# Connectors.net
KiCad netlist of a schematic drawn in Altium Designer
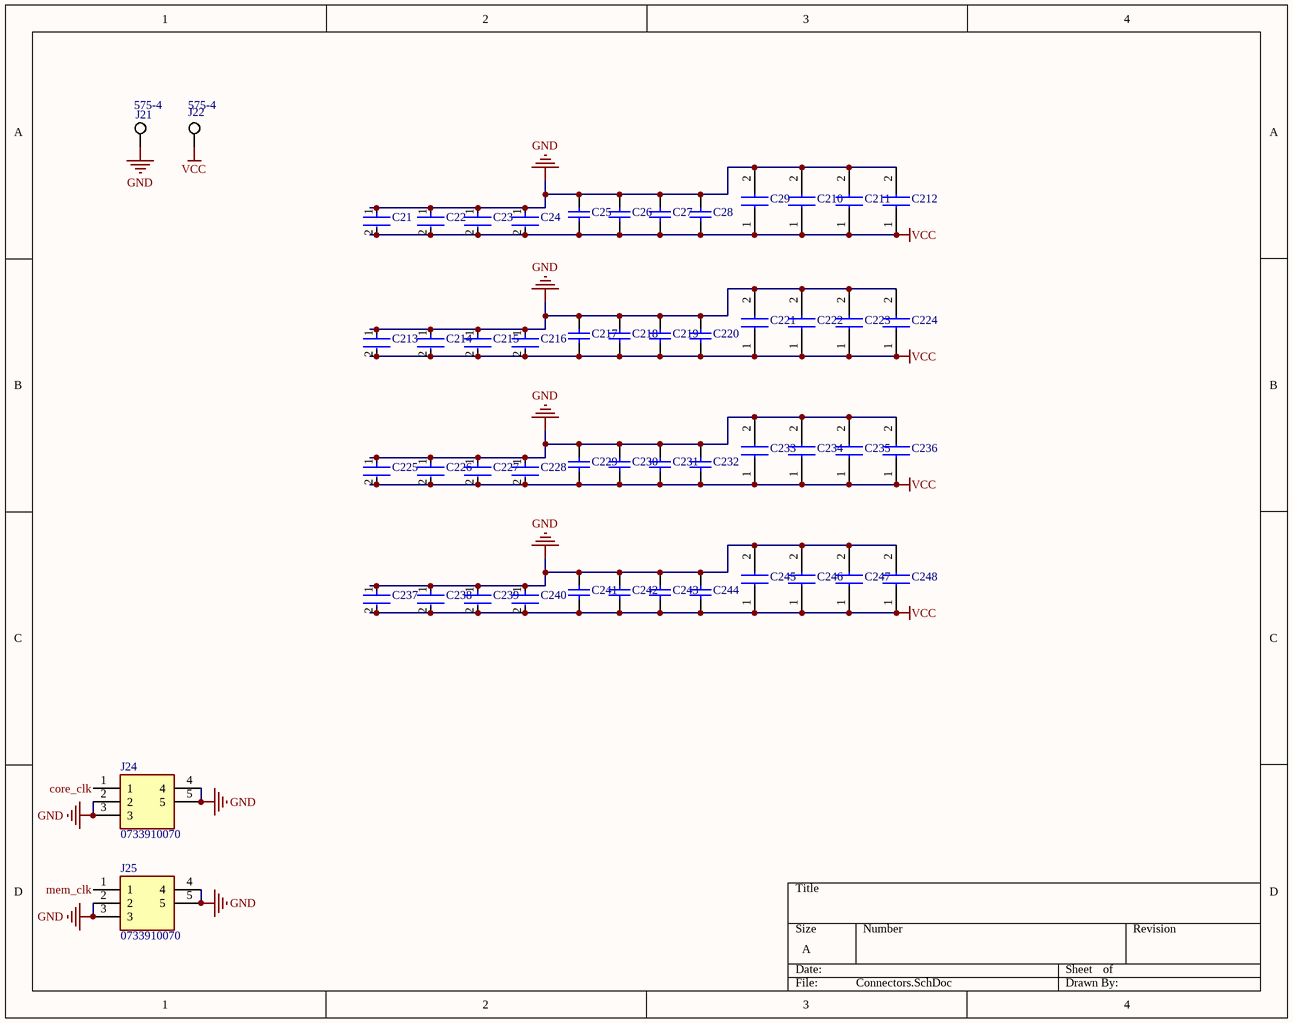
[diagram p0: Connectors.SchDoc]

(export (version "E")
  (design (tool "Eeschema 10.0.6"))
  (components
    (comp (ref "C21")
      (value "UMK105BJ104KV-F")
      (footprint "FP-0402-L_1_0_0_05-W_0_5-IPC_B")
      (description "None")
      (fields (field (name "TOLERANCE") "10%"))
      (libsource (lib "Altium Content Vault") (part "b4654b650e69147ec39a6b967a45e02"))
    )
    (comp (ref "C22")
      (value "UMK105BJ104KV-F")
      (footprint "FP-0402-L_1_0_0_05-W_0_5-IPC_B")
      (description "None")
      (fields (field (name "TOLERANCE") "10%"))
      (libsource (lib "Altium Content Vault") (part "b4654b650e69147ec39a6b967a45e02"))
    )
    (comp (ref "C23")
      (value "UMK105BJ104KV-F")
      (footprint "FP-0402-L_1_0_0_05-W_0_5-IPC_B")
      (description "None")
      (fields (field (name "TOLERANCE") "10%"))
      (libsource (lib "Altium Content Vault") (part "b4654b650e69147ec39a6b967a45e02"))
    )
    (comp (ref "C24")
      (value "UMK105BJ104KV-F")
      (footprint "FP-0402-L_1_0_0_05-W_0_5-IPC_B")
      (description "None")
      (fields (field (name "TOLERANCE") "10%"))
      (libsource (lib "Altium Content Vault") (part "b4654b650e69147ec39a6b967a45e02"))
    )
    (comp (ref "C25")
      (value "LMK107B7105KA-T")
      (footprint "CAPC1608X90X35NL10T25")
      (description "None")
      (fields (field (name "TOLERANCE") "10%"))
      (libsource (lib "Altium Content Vault") (part "CAP-NP-2"))
    )
    (comp (ref "C26")
      (value "LMK107B7105KA-T")
      (footprint "CAPC1608X90X35NL10T25")
      (description "None")
      (fields (field (name "TOLERANCE") "10%"))
      (libsource (lib "Altium Content Vault") (part "CAP-NP-2"))
    )
    (comp (ref "C27")
      (value "LMK107B7105KA-T")
      (footprint "CAPC1608X90X35NL10T25")
      (description "None")
      (fields (field (name "TOLERANCE") "10%"))
      (libsource (lib "Altium Content Vault") (part "CAP-NP-2"))
    )
    (comp (ref "C28")
      (value "LMK107B7105KA-T")
      (footprint "CAPC1608X90X35NL10T25")
      (description "None")
      (fields (field (name "TOLERANCE") "10%"))
      (libsource (lib "Altium Content Vault") (part "CAP-NP-2"))
    )
    (comp (ref "C29")
      (value "KGM15CR51A106MT")
      (footprint "SamacSys:CAPC1608X100N")
      (description "Capacitor")
      (libsource (lib "*") (part "KGM15CR51A106MT"))
    )
    (comp (ref "C210")
      (value "KGM15CR51A106MT")
      (footprint "SamacSys:CAPC1608X100N")
      (description "Capacitor")
      (libsource (lib "*") (part "KGM15CR51A106MT"))
    )
    (comp (ref "C211")
      (value "KGM15CR51A106MT")
      (footprint "SamacSys:CAPC1608X100N")
      (description "Capacitor")
      (libsource (lib "*") (part "KGM15CR51A106MT"))
    )
    (comp (ref "C212")
      (value "KGM15CR51A106MT")
      (footprint "SamacSys:CAPC1608X100N")
      (description "Capacitor")
      (libsource (lib "*") (part "KGM15CR51A106MT"))
    )
    (comp (ref "C213")
      (value "UMK105BJ104KV-F")
      (footprint "FP-0402-L_1_0_0_05-W_0_5-IPC_B")
      (description "None")
      (fields (field (name "TOLERANCE") "10%"))
      (libsource (lib "Altium Content Vault") (part "b4654b650e69147ec39a6b967a45e02"))
    )
    (comp (ref "C214")
      (value "UMK105BJ104KV-F")
      (footprint "FP-0402-L_1_0_0_05-W_0_5-IPC_B")
      (description "None")
      (fields (field (name "TOLERANCE") "10%"))
      (libsource (lib "Altium Content Vault") (part "b4654b650e69147ec39a6b967a45e02"))
    )
    (comp (ref "C215")
      (value "UMK105BJ104KV-F")
      (footprint "FP-0402-L_1_0_0_05-W_0_5-IPC_B")
      (description "None")
      (fields (field (name "TOLERANCE") "10%"))
      (libsource (lib "Altium Content Vault") (part "b4654b650e69147ec39a6b967a45e02"))
    )
    (comp (ref "C216")
      (value "UMK105BJ104KV-F")
      (footprint "FP-0402-L_1_0_0_05-W_0_5-IPC_B")
      (description "None")
      (fields (field (name "TOLERANCE") "10%"))
      (libsource (lib "Altium Content Vault") (part "b4654b650e69147ec39a6b967a45e02"))
    )
    (comp (ref "C217")
      (value "LMK107B7105KA-T")
      (footprint "CAPC1608X90X35NL10T25")
      (description "None")
      (fields (field (name "TOLERANCE") "10%"))
      (libsource (lib "Altium Content Vault") (part "CAP-NP-2"))
    )
    (comp (ref "C218")
      (value "LMK107B7105KA-T")
      (footprint "CAPC1608X90X35NL10T25")
      (description "None")
      (fields (field (name "TOLERANCE") "10%"))
      (libsource (lib "Altium Content Vault") (part "CAP-NP-2"))
    )
    (comp (ref "C219")
      (value "LMK107B7105KA-T")
      (footprint "CAPC1608X90X35NL10T25")
      (description "None")
      (fields (field (name "TOLERANCE") "10%"))
      (libsource (lib "Altium Content Vault") (part "CAP-NP-2"))
    )
    (comp (ref "C220")
      (value "LMK107B7105KA-T")
      (footprint "CAPC1608X90X35NL10T25")
      (description "None")
      (fields (field (name "TOLERANCE") "10%"))
      (libsource (lib "Altium Content Vault") (part "CAP-NP-2"))
    )
    (comp (ref "C221")
      (value "KGM15CR51A106MT")
      (footprint "SamacSys:CAPC1608X100N")
      (description "Capacitor")
      (libsource (lib "*") (part "KGM15CR51A106MT"))
    )
    (comp (ref "C222")
      (value "KGM15CR51A106MT")
      (footprint "SamacSys:CAPC1608X100N")
      (description "Capacitor")
      (libsource (lib "*") (part "KGM15CR51A106MT"))
    )
    (comp (ref "C223")
      (value "KGM15CR51A106MT")
      (footprint "SamacSys:CAPC1608X100N")
      (description "Capacitor")
      (libsource (lib "*") (part "KGM15CR51A106MT"))
    )
    (comp (ref "C224")
      (value "KGM15CR51A106MT")
      (footprint "SamacSys:CAPC1608X100N")
      (description "Capacitor")
      (libsource (lib "*") (part "KGM15CR51A106MT"))
    )
    (comp (ref "C225")
      (value "UMK105BJ104KV-F")
      (footprint "FP-0402-L_1_0_0_05-W_0_5-IPC_B")
      (description "None")
      (fields (field (name "TOLERANCE") "10%"))
      (libsource (lib "Altium Content Vault") (part "b4654b650e69147ec39a6b967a45e02"))
    )
    (comp (ref "C226")
      (value "UMK105BJ104KV-F")
      (footprint "FP-0402-L_1_0_0_05-W_0_5-IPC_B")
      (description "None")
      (fields (field (name "TOLERANCE") "10%"))
      (libsource (lib "Altium Content Vault") (part "b4654b650e69147ec39a6b967a45e02"))
    )
    (comp (ref "C227")
      (value "UMK105BJ104KV-F")
      (footprint "FP-0402-L_1_0_0_05-W_0_5-IPC_B")
      (description "None")
      (fields (field (name "TOLERANCE") "10%"))
      (libsource (lib "Altium Content Vault") (part "b4654b650e69147ec39a6b967a45e02"))
    )
    (comp (ref "C228")
      (value "UMK105BJ104KV-F")
      (footprint "FP-0402-L_1_0_0_05-W_0_5-IPC_B")
      (description "None")
      (fields (field (name "TOLERANCE") "10%"))
      (libsource (lib "Altium Content Vault") (part "b4654b650e69147ec39a6b967a45e02"))
    )
    (comp (ref "C229")
      (value "LMK107B7105KA-T")
      (footprint "CAPC1608X90X35NL10T25")
      (description "None")
      (fields (field (name "TOLERANCE") "10%"))
      (libsource (lib "Altium Content Vault") (part "CAP-NP-2"))
    )
    (comp (ref "C230")
      (value "LMK107B7105KA-T")
      (footprint "CAPC1608X90X35NL10T25")
      (description "None")
      (fields (field (name "TOLERANCE") "10%"))
      (libsource (lib "Altium Content Vault") (part "CAP-NP-2"))
    )
    (comp (ref "C231")
      (value "LMK107B7105KA-T")
      (footprint "CAPC1608X90X35NL10T25")
      (description "None")
      (fields (field (name "TOLERANCE") "10%"))
      (libsource (lib "Altium Content Vault") (part "CAP-NP-2"))
    )
    (comp (ref "C232")
      (value "LMK107B7105KA-T")
      (footprint "CAPC1608X90X35NL10T25")
      (description "None")
      (fields (field (name "TOLERANCE") "10%"))
      (libsource (lib "Altium Content Vault") (part "CAP-NP-2"))
    )
    (comp (ref "C233")
      (value "KGM15CR51A106MT")
      (footprint "SamacSys:CAPC1608X100N")
      (description "Capacitor")
      (libsource (lib "*") (part "KGM15CR51A106MT"))
    )
    (comp (ref "C234")
      (value "KGM15CR51A106MT")
      (footprint "SamacSys:CAPC1608X100N")
      (description "Capacitor")
      (libsource (lib "*") (part "KGM15CR51A106MT"))
    )
    (comp (ref "C235")
      (value "KGM15CR51A106MT")
      (footprint "SamacSys:CAPC1608X100N")
      (description "Capacitor")
      (libsource (lib "*") (part "KGM15CR51A106MT"))
    )
    (comp (ref "C236")
      (value "KGM15CR51A106MT")
      (footprint "SamacSys:CAPC1608X100N")
      (description "Capacitor")
      (libsource (lib "*") (part "KGM15CR51A106MT"))
    )
    (comp (ref "C237")
      (value "UMK105BJ104KV-F")
      (footprint "FP-0402-L_1_0_0_05-W_0_5-IPC_B")
      (description "None")
      (fields (field (name "TOLERANCE") "10%"))
      (libsource (lib "Altium Content Vault") (part "b4654b650e69147ec39a6b967a45e02"))
    )
    (comp (ref "C238")
      (value "UMK105BJ104KV-F")
      (footprint "FP-0402-L_1_0_0_05-W_0_5-IPC_B")
      (description "None")
      (fields (field (name "TOLERANCE") "10%"))
      (libsource (lib "Altium Content Vault") (part "b4654b650e69147ec39a6b967a45e02"))
    )
    (comp (ref "C239")
      (value "UMK105BJ104KV-F")
      (footprint "FP-0402-L_1_0_0_05-W_0_5-IPC_B")
      (description "None")
      (fields (field (name "TOLERANCE") "10%"))
      (libsource (lib "Altium Content Vault") (part "b4654b650e69147ec39a6b967a45e02"))
    )
    (comp (ref "C240")
      (value "UMK105BJ104KV-F")
      (footprint "FP-0402-L_1_0_0_05-W_0_5-IPC_B")
      (description "None")
      (fields (field (name "TOLERANCE") "10%"))
      (libsource (lib "Altium Content Vault") (part "b4654b650e69147ec39a6b967a45e02"))
    )
    (comp (ref "C241")
      (value "LMK107B7105KA-T")
      (footprint "CAPC1608X90X35NL10T25")
      (description "None")
      (fields (field (name "TOLERANCE") "10%"))
      (libsource (lib "Altium Content Vault") (part "CAP-NP-2"))
    )
    (comp (ref "C242")
      (value "LMK107B7105KA-T")
      (footprint "CAPC1608X90X35NL10T25")
      (description "None")
      (fields (field (name "TOLERANCE") "10%"))
      (libsource (lib "Altium Content Vault") (part "CAP-NP-2"))
    )
    (comp (ref "C243")
      (value "LMK107B7105KA-T")
      (footprint "CAPC1608X90X35NL10T25")
      (description "None")
      (fields (field (name "TOLERANCE") "10%"))
      (libsource (lib "Altium Content Vault") (part "CAP-NP-2"))
    )
    (comp (ref "C244")
      (value "LMK107B7105KA-T")
      (footprint "CAPC1608X90X35NL10T25")
      (description "None")
      (fields (field (name "TOLERANCE") "10%"))
      (libsource (lib "Altium Content Vault") (part "CAP-NP-2"))
    )
    (comp (ref "C245")
      (value "KGM15CR51A106MT")
      (footprint "SamacSys:CAPC1608X100N")
      (description "Capacitor")
      (libsource (lib "*") (part "KGM15CR51A106MT"))
    )
    (comp (ref "C246")
      (value "KGM15CR51A106MT")
      (footprint "SamacSys:CAPC1608X100N")
      (description "Capacitor")
      (libsource (lib "*") (part "KGM15CR51A106MT"))
    )
    (comp (ref "C247")
      (value "KGM15CR51A106MT")
      (footprint "SamacSys:CAPC1608X100N")
      (description "Capacitor")
      (libsource (lib "*") (part "KGM15CR51A106MT"))
    )
    (comp (ref "C248")
      (value "KGM15CR51A106MT")
      (footprint "SamacSys:CAPC1608X100N")
      (description "Capacitor")
      (libsource (lib "*") (part "KGM15CR51A106MT"))
    )
    (comp (ref "J21")
      (value "575-4")
      (footprint "KSTN-575-4")
      (description "Banana Jack, Non-Insulated, 1-Pin THD, RoHS, Bulk")
      (fields (field (name "MANUFACTURER") "Keystone-Electronics"))
      (libsource (lib "Altium Content Vault") (part "TESTPOINT_WHITE"))
    )
    (comp (ref "J22")
      (value "575-4")
      (footprint "KSTN-575-4")
      (description "Banana Jack, Non-Insulated, 1-Pin THD, RoHS, Bulk")
      (fields (field (name "MANUFACTURER") "Keystone-Electronics"))
      (libsource (lib "Altium Content Vault") (part "TESTPOINT_WHITE"))
    )
    (comp (ref "J24")
      (value "0733910070")
      (footprint "SamacSys:0733910070")
      (description "Connector")
      (libsource (lib "*") (part "0733910070"))
    )
    (comp (ref "J25")
      (value "0733910070")
      (footprint "SamacSys:0733910070")
      (description "Connector")
      (libsource (lib "*") (part "0733910070"))
    )
  )
  (nets
    (net (code "1") (name "/core_clk") (class "Default")
      (node (ref "J24") (pin "1") (pinfunction "1_1") (pintype "passive"))
    )
    (net (code "2") (name "/mem_clk") (class "Default")
      (node (ref "J25") (pin "1") (pinfunction "1_1") (pintype "passive"))
    )
    (net (code "3") (name "GND") (class "Default")
      (node (ref "C21") (pin "1") (pinfunction "1_1") (pintype "passive"))
      (node (ref "C210") (pin "2") (pinfunction "2_2") (pintype "passive"))
      (node (ref "C211") (pin "2") (pinfunction "2_2") (pintype "passive"))
      (node (ref "C212") (pin "2") (pinfunction "2_2") (pintype "passive"))
      (node (ref "C213") (pin "1") (pinfunction "1_1") (pintype "passive"))
      (node (ref "C214") (pin "1") (pinfunction "1_1") (pintype "passive"))
      (node (ref "C215") (pin "1") (pinfunction "1_1") (pintype "passive"))
      (node (ref "C216") (pin "1") (pinfunction "1_1") (pintype "passive"))
      (node (ref "C217") (pin "2") (pinfunction "2_2") (pintype "passive"))
      (node (ref "C218") (pin "2") (pinfunction "2_2") (pintype "passive"))
      (node (ref "C219") (pin "2") (pinfunction "2_2") (pintype "passive"))
      (node (ref "C22") (pin "1") (pinfunction "1_1") (pintype "passive"))
      (node (ref "C220") (pin "2") (pinfunction "2_2") (pintype "passive"))
      (node (ref "C221") (pin "2") (pinfunction "2_2") (pintype "passive"))
      (node (ref "C222") (pin "2") (pinfunction "2_2") (pintype "passive"))
      (node (ref "C223") (pin "2") (pinfunction "2_2") (pintype "passive"))
      (node (ref "C224") (pin "2") (pinfunction "2_2") (pintype "passive"))
      (node (ref "C225") (pin "1") (pinfunction "1_1") (pintype "passive"))
      (node (ref "C226") (pin "1") (pinfunction "1_1") (pintype "passive"))
      (node (ref "C227") (pin "1") (pinfunction "1_1") (pintype "passive"))
      (node (ref "C228") (pin "1") (pinfunction "1_1") (pintype "passive"))
      (node (ref "C229") (pin "2") (pinfunction "2_2") (pintype "passive"))
      (node (ref "C23") (pin "1") (pinfunction "1_1") (pintype "passive"))
      (node (ref "C230") (pin "2") (pinfunction "2_2") (pintype "passive"))
      (node (ref "C231") (pin "2") (pinfunction "2_2") (pintype "passive"))
      (node (ref "C232") (pin "2") (pinfunction "2_2") (pintype "passive"))
      (node (ref "C233") (pin "2") (pinfunction "2_2") (pintype "passive"))
      (node (ref "C234") (pin "2") (pinfunction "2_2") (pintype "passive"))
      (node (ref "C235") (pin "2") (pinfunction "2_2") (pintype "passive"))
      (node (ref "C236") (pin "2") (pinfunction "2_2") (pintype "passive"))
      (node (ref "C237") (pin "1") (pinfunction "1_1") (pintype "passive"))
      (node (ref "C238") (pin "1") (pinfunction "1_1") (pintype "passive"))
      (node (ref "C239") (pin "1") (pinfunction "1_1") (pintype "passive"))
      (node (ref "C24") (pin "1") (pinfunction "1_1") (pintype "passive"))
      (node (ref "C240") (pin "1") (pinfunction "1_1") (pintype "passive"))
      (node (ref "C241") (pin "2") (pinfunction "2_2") (pintype "passive"))
      (node (ref "C242") (pin "2") (pinfunction "2_2") (pintype "passive"))
      (node (ref "C243") (pin "2") (pinfunction "2_2") (pintype "passive"))
      (node (ref "C244") (pin "2") (pinfunction "2_2") (pintype "passive"))
      (node (ref "C245") (pin "2") (pinfunction "2_2") (pintype "passive"))
      (node (ref "C246") (pin "2") (pinfunction "2_2") (pintype "passive"))
      (node (ref "C247") (pin "2") (pinfunction "2_2") (pintype "passive"))
      (node (ref "C248") (pin "2") (pinfunction "2_2") (pintype "passive"))
      (node (ref "C25") (pin "2") (pinfunction "2_2") (pintype "passive"))
      (node (ref "C26") (pin "2") (pinfunction "2_2") (pintype "passive"))
      (node (ref "C27") (pin "2") (pinfunction "2_2") (pintype "passive"))
      (node (ref "C28") (pin "2") (pinfunction "2_2") (pintype "passive"))
      (node (ref "C29") (pin "2") (pinfunction "2_2") (pintype "passive"))
      (node (ref "J21") (pin "1") (pinfunction "1_1") (pintype "passive"))
      (node (ref "J24") (pin "2") (pinfunction "2_2") (pintype "passive"))
      (node (ref "J24") (pin "3") (pinfunction "3_3") (pintype "passive"))
      (node (ref "J24") (pin "4") (pinfunction "4_4") (pintype "passive"))
      (node (ref "J24") (pin "5") (pinfunction "5_5") (pintype "passive"))
      (node (ref "J25") (pin "2") (pinfunction "2_2") (pintype "passive"))
      (node (ref "J25") (pin "3") (pinfunction "3_3") (pintype "passive"))
      (node (ref "J25") (pin "4") (pinfunction "4_4") (pintype "passive"))
      (node (ref "J25") (pin "5") (pinfunction "5_5") (pintype "passive"))
    )
    (net (code "4") (name "VCC") (class "Default")
      (node (ref "C21") (pin "2") (pinfunction "2_2") (pintype "passive"))
      (node (ref "C210") (pin "1") (pinfunction "1_1") (pintype "passive"))
      (node (ref "C211") (pin "1") (pinfunction "1_1") (pintype "passive"))
      (node (ref "C212") (pin "1") (pinfunction "1_1") (pintype "passive"))
      (node (ref "C213") (pin "2") (pinfunction "2_2") (pintype "passive"))
      (node (ref "C214") (pin "2") (pinfunction "2_2") (pintype "passive"))
      (node (ref "C215") (pin "2") (pinfunction "2_2") (pintype "passive"))
      (node (ref "C216") (pin "2") (pinfunction "2_2") (pintype "passive"))
      (node (ref "C217") (pin "1") (pinfunction "1_1") (pintype "passive"))
      (node (ref "C218") (pin "1") (pinfunction "1_1") (pintype "passive"))
      (node (ref "C219") (pin "1") (pinfunction "1_1") (pintype "passive"))
      (node (ref "C22") (pin "2") (pinfunction "2_2") (pintype "passive"))
      (node (ref "C220") (pin "1") (pinfunction "1_1") (pintype "passive"))
      (node (ref "C221") (pin "1") (pinfunction "1_1") (pintype "passive"))
      (node (ref "C222") (pin "1") (pinfunction "1_1") (pintype "passive"))
      (node (ref "C223") (pin "1") (pinfunction "1_1") (pintype "passive"))
      (node (ref "C224") (pin "1") (pinfunction "1_1") (pintype "passive"))
      (node (ref "C225") (pin "2") (pinfunction "2_2") (pintype "passive"))
      (node (ref "C226") (pin "2") (pinfunction "2_2") (pintype "passive"))
      (node (ref "C227") (pin "2") (pinfunction "2_2") (pintype "passive"))
      (node (ref "C228") (pin "2") (pinfunction "2_2") (pintype "passive"))
      (node (ref "C229") (pin "1") (pinfunction "1_1") (pintype "passive"))
      (node (ref "C23") (pin "2") (pinfunction "2_2") (pintype "passive"))
      (node (ref "C230") (pin "1") (pinfunction "1_1") (pintype "passive"))
      (node (ref "C231") (pin "1") (pinfunction "1_1") (pintype "passive"))
      (node (ref "C232") (pin "1") (pinfunction "1_1") (pintype "passive"))
      (node (ref "C233") (pin "1") (pinfunction "1_1") (pintype "passive"))
      (node (ref "C234") (pin "1") (pinfunction "1_1") (pintype "passive"))
      (node (ref "C235") (pin "1") (pinfunction "1_1") (pintype "passive"))
      (node (ref "C236") (pin "1") (pinfunction "1_1") (pintype "passive"))
      (node (ref "C237") (pin "2") (pinfunction "2_2") (pintype "passive"))
      (node (ref "C238") (pin "2") (pinfunction "2_2") (pintype "passive"))
      (node (ref "C239") (pin "2") (pinfunction "2_2") (pintype "passive"))
      (node (ref "C24") (pin "2") (pinfunction "2_2") (pintype "passive"))
      (node (ref "C240") (pin "2") (pinfunction "2_2") (pintype "passive"))
      (node (ref "C241") (pin "1") (pinfunction "1_1") (pintype "passive"))
      (node (ref "C242") (pin "1") (pinfunction "1_1") (pintype "passive"))
      (node (ref "C243") (pin "1") (pinfunction "1_1") (pintype "passive"))
      (node (ref "C244") (pin "1") (pinfunction "1_1") (pintype "passive"))
      (node (ref "C245") (pin "1") (pinfunction "1_1") (pintype "passive"))
      (node (ref "C246") (pin "1") (pinfunction "1_1") (pintype "passive"))
      (node (ref "C247") (pin "1") (pinfunction "1_1") (pintype "passive"))
      (node (ref "C248") (pin "1") (pinfunction "1_1") (pintype "passive"))
      (node (ref "C25") (pin "1") (pinfunction "1_1") (pintype "passive"))
      (node (ref "C26") (pin "1") (pinfunction "1_1") (pintype "passive"))
      (node (ref "C27") (pin "1") (pinfunction "1_1") (pintype "passive"))
      (node (ref "C28") (pin "1") (pinfunction "1_1") (pintype "passive"))
      (node (ref "C29") (pin "1") (pinfunction "1_1") (pintype "passive"))
      (node (ref "J22") (pin "1") (pinfunction "1_1") (pintype "passive"))
    )
  )
)
